# Hard.net
KiCad netlist of a schematic drawn in Altium Designer
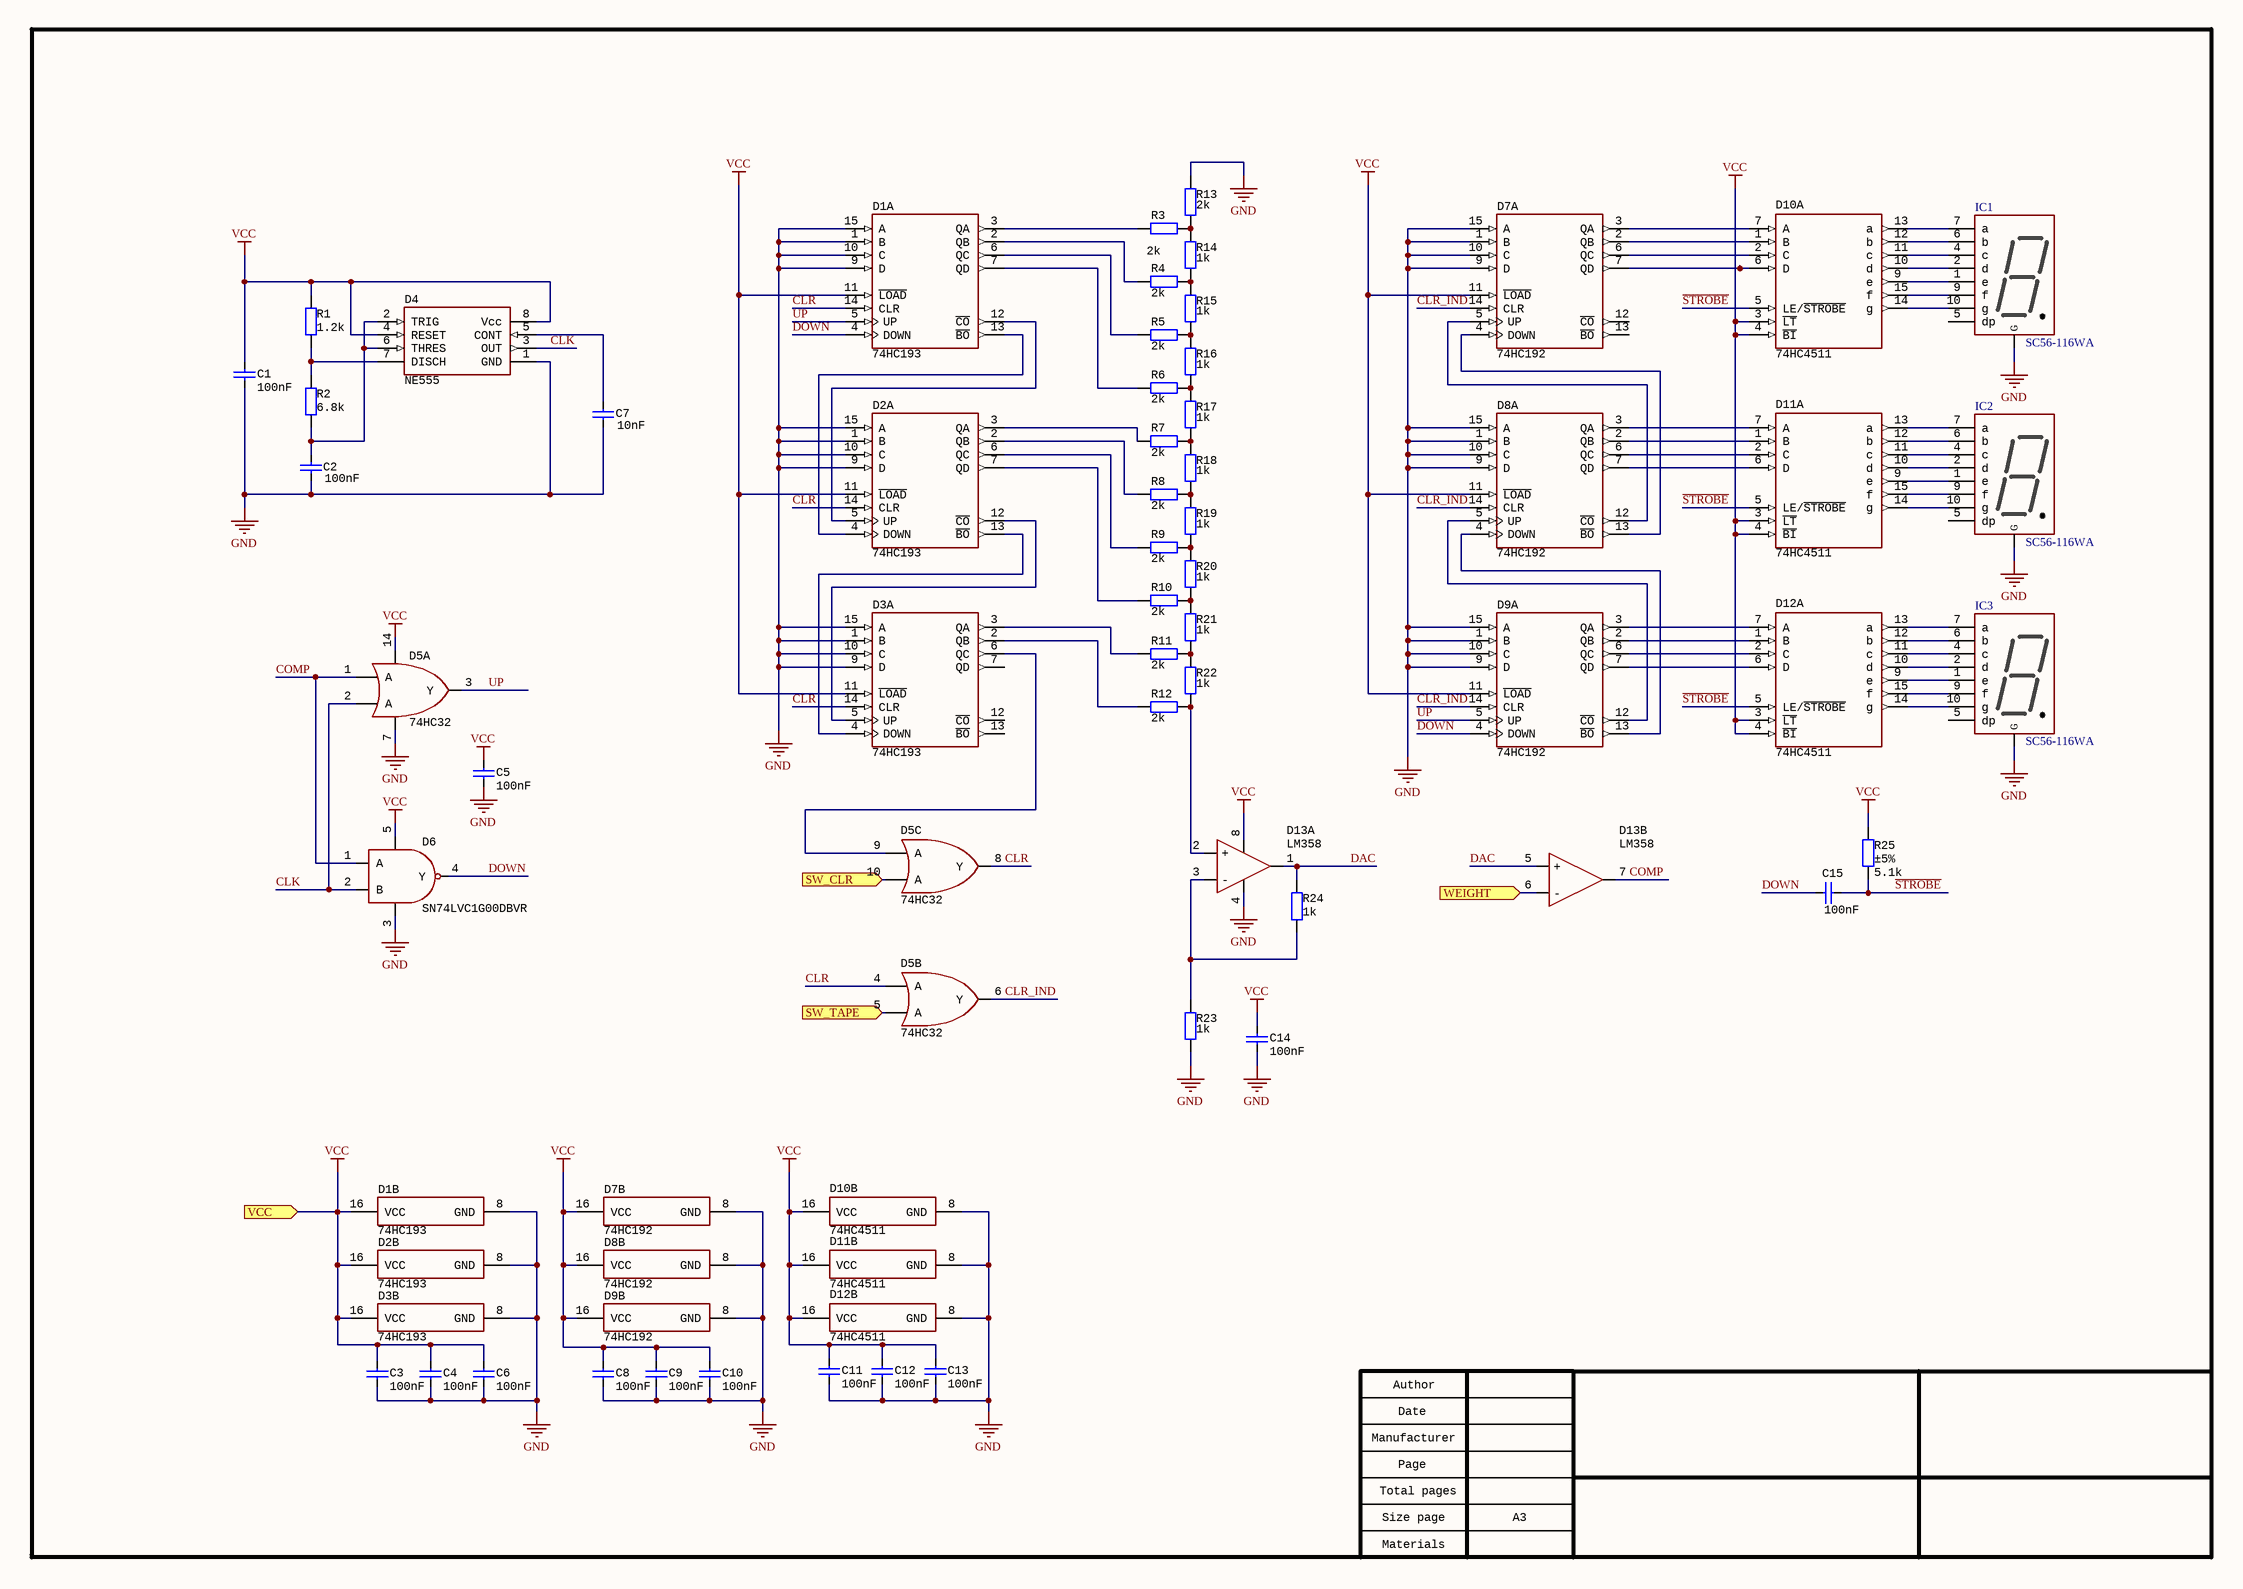
[diagram p0: Hard.SchDoc]

(export (version "E")
  (design (tool "Eeschema 10.0.6"))
  (components
    (comp (ref "C1")
      (value "100nF")
      (footprint "CAP: ECHU(X) K (0603)")
      (fields
        (field (name "MANUFACTURER") "Epcos")
        (field (name "PARTNUMBER") "B32774D4106K000")
        (field (name "VALUEMANUFACTURERPARTNUMBER") "Film capacitor, 100nF, 15VDC, ±10%, 10.9mOhm, 31.5x15 mm, -40...+105°C")
      )
      (libsource (lib "capacitor") (part "Film"))
    )
    (comp (ref "C2")
      (value "100nF")
      (footprint "CAP: ECHU(X) K (0603)")
      (fields
        (field (name "MANUFACTURER") "Epcos")
        (field (name "PARTNUMBER") "B32774D4106K000")
        (field (name "VALUEMANUFACTURERPARTNUMBER") "Film capacitor, 100nF, 15VDC, ±10%, 10.9mOhm, 31.5x15 mm, -40...+105°C")
      )
      (libsource (lib "capacitor") (part "Film"))
    )
    (comp (ref "C3")
      (value "100nF")
      (footprint "CAP: ECHU(X) K (0603)")
      (fields
        (field (name "MANUFACTURER") "Epcos")
        (field (name "PARTNUMBER") "B32774D4106K000")
        (field (name "VALUEMANUFACTURERPARTNUMBER") "Film capacitor, 100nF, 15VDC, ±10%, 10.9mOhm, 31.5x15 mm, -40...+105°C")
      )
      (libsource (lib "capacitor") (part "Film"))
    )
    (comp (ref "C4")
      (value "100nF")
      (footprint "CAP: ECHU(X) K (0603)")
      (fields
        (field (name "MANUFACTURER") "Epcos")
        (field (name "PARTNUMBER") "B32774D4106K000")
        (field (name "VALUEMANUFACTURERPARTNUMBER") "Film capacitor, 100nF, 15VDC, ±10%, 10.9mOhm, 31.5x15 mm, -40...+105°C")
      )
      (libsource (lib "capacitor") (part "Film"))
    )
    (comp (ref "C5")
      (value "100nF")
      (footprint "CAP: ECHU(X) K (0603)")
      (fields
        (field (name "MANUFACTURER") "Epcos")
        (field (name "PARTNUMBER") "B32774D4106K000")
        (field (name "VALUEMANUFACTURERPARTNUMBER") "Film capacitor, 100nF, 15VDC, ±10%, 10.9mOhm, 31.5x15 mm, -40...+105°C")
      )
      (libsource (lib "capacitor") (part "Film"))
    )
    (comp (ref "C6")
      (value "100nF")
      (footprint "CAP: ECHU(X) K (0603)")
      (fields
        (field (name "MANUFACTURER") "Epcos")
        (field (name "PARTNUMBER") "B32774D4106K000")
        (field (name "VALUEMANUFACTURERPARTNUMBER") "Film capacitor, 100nF, 15VDC, ±10%, 10.9mOhm, 31.5x15 mm, -40...+105°C")
      )
      (libsource (lib "capacitor") (part "Film"))
    )
    (comp (ref "C7")
      (value "10nF")
      (footprint "CAP: ECHU(X) K (0603)")
      (fields
        (field (name "MANUFACTURER") "Epcos")
        (field (name "PARTNUMBER") "B32774D4106K000")
        (field (name "VALUEMANUFACTURERPARTNUMBER") "Film capacitor, 10nF, 15VDC, ±10%, 10.9mOhm, 31.5x15 mm, -40...+105°C")
      )
      (libsource (lib "capacitor") (part "Film"))
    )
    (comp (ref "C8")
      (value "100nF")
      (footprint "CAP: ECHU(X) K (0603)")
      (fields
        (field (name "MANUFACTURER") "Epcos")
        (field (name "PARTNUMBER") "B32774D4106K000")
        (field (name "VALUEMANUFACTURERPARTNUMBER") "Film capacitor, 100nF, 15VDC, ±10%, 10.9mOhm, 31.5x15 mm, -40...+105°C")
      )
      (libsource (lib "capacitor") (part "Film"))
    )
    (comp (ref "C9")
      (value "100nF")
      (footprint "CAP: ECHU(X) K (0603)")
      (fields
        (field (name "MANUFACTURER") "Epcos")
        (field (name "PARTNUMBER") "B32774D4106K000")
        (field (name "VALUEMANUFACTURERPARTNUMBER") "Film capacitor, 100nF, 15VDC, ±10%, 10.9mOhm, 31.5x15 mm, -40...+105°C")
      )
      (libsource (lib "capacitor") (part "Film"))
    )
    (comp (ref "C10")
      (value "100nF")
      (footprint "CAP: ECHU(X) K (0603)")
      (fields
        (field (name "MANUFACTURER") "Epcos")
        (field (name "PARTNUMBER") "B32774D4106K000")
        (field (name "VALUEMANUFACTURERPARTNUMBER") "Film capacitor, 100nF, 15VDC, ±10%, 10.9mOhm, 31.5x15 mm, -40...+105°C")
      )
      (libsource (lib "capacitor") (part "Film"))
    )
    (comp (ref "C11")
      (value "100nF")
      (footprint "CAP: ECHU(X) K (0603)")
      (fields
        (field (name "MANUFACTURER") "Epcos")
        (field (name "PARTNUMBER") "B32774D4106K000")
        (field (name "VALUEMANUFACTURERPARTNUMBER") "Film capacitor, 100nF, 15VDC, ±10%, 10.9mOhm, 31.5x15 mm, -40...+105°C")
      )
      (libsource (lib "capacitor") (part "Film"))
    )
    (comp (ref "C12")
      (value "100nF")
      (footprint "CAP: ECHU(X) K (0603)")
      (fields
        (field (name "MANUFACTURER") "Epcos")
        (field (name "PARTNUMBER") "B32774D4106K000")
        (field (name "VALUEMANUFACTURERPARTNUMBER") "Film capacitor, 100nF, 15VDC, ±10%, 10.9mOhm, 31.5x15 mm, -40...+105°C")
      )
      (libsource (lib "capacitor") (part "Film"))
    )
    (comp (ref "C13")
      (value "100nF")
      (footprint "CAP: ECHU(X) K (0603)")
      (fields
        (field (name "MANUFACTURER") "Epcos")
        (field (name "PARTNUMBER") "B32774D4106K000")
        (field (name "VALUEMANUFACTURERPARTNUMBER") "Film capacitor, 100nF, 15VDC, ±10%, 10.9mOhm, 31.5x15 mm, -40...+105°C")
      )
      (libsource (lib "capacitor") (part "Film"))
    )
    (comp (ref "C14")
      (value "100nF")
      (footprint "CAP: ECHU(X) K (0603)")
      (fields
        (field (name "MANUFACTURER") "Epcos")
        (field (name "PARTNUMBER") "B32774D4106K000")
        (field (name "VALUEMANUFACTURERPARTNUMBER") "Film capacitor, 100nF, 15VDC, ±10%, 10.9mOhm, 31.5x15 mm, -40...+105°C")
      )
      (libsource (lib "capacitor") (part "Film"))
    )
    (comp (ref "C15")
      (value "100nF")
      (footprint "CAP: ECHU(X) K (0603)")
      (fields
        (field (name "MANUFACTURER") "Epcos")
        (field (name "PARTNUMBER") "B32774D4106K000")
        (field (name "VALUEMANUFACTURERPARTNUMBER") "Film capacitor, 100nF, 15VDC, ±10%, 10.9mOhm, 31.5x15 mm, -40...+105°C")
      )
      (libsource (lib "capacitor") (part "Film"))
    )
    (comp (ref "D1")
      (value "74HC193")
      (footprint "16-SO")
      (description "Counter")
      (libsource (lib "ic-logic") (part "74HC193"))
    )
    (comp (ref "D2")
      (value "74HC193")
      (footprint "16-SO")
      (description "Counter")
      (libsource (lib "ic-logic") (part "74HC193"))
    )
    (comp (ref "D3")
      (value "74HC193")
      (footprint "16-SO")
      (description "Counter")
      (libsource (lib "ic-logic") (part "74HC193"))
    )
    (comp (ref "D4")
      (value "NE555")
      (footprint "8-SOIC")
      (description "Counter")
      (libsource (lib "ic-logic") (part "NE555"))
    )
    (comp (ref "D5")
      (value "~")
      (footprint "14-SOIC")
      (description "OR")
      (fields
        (field (name "MANUFACTURER") "Texas Instruments")
        (field (name "VALUEMANUFACTURERPARTNUMBER") "IC logic OR, 1.65...5.5V, -40...+125°C, SOT23-6")
        (field (name "PARTNUMBER") "74HC32")
      )
      (libsource (lib "ic-logic") (part "74HC32"))
    )
    (comp (ref "D6")
      (value "~")
      (footprint "SOT23-5")
      (description "NAND")
      (fields
        (field (name "MANUFACTURER") "Texas Instruments")
        (field (name "VALUEMANUFACTURERPARTNUMBER") "IC logic AND, 1.65...5.5V, -40...+125°C, SC-70-5")
        (field (name "PARTNUMBER") "SN74LVC1G00DBVR")
      )
      (libsource (lib "ic-logic") (part "SN74LVC1G00DBVR"))
    )
    (comp (ref "D7")
      (value "74HC192")
      (footprint "16-SO")
      (description "Counter")
      (libsource (lib "ic-logic") (part "74HC192"))
    )
    (comp (ref "D8")
      (value "74HC192")
      (footprint "16-SO")
      (description "Counter")
      (libsource (lib "ic-logic") (part "74HC192"))
    )
    (comp (ref "D9")
      (value "74HC192")
      (footprint "16-SO")
      (description "Counter")
      (libsource (lib "ic-logic") (part "74HC192"))
    )
    (comp (ref "D10")
      (value "74HC4511")
      (footprint "16-SO")
      (description "7-seg decoder")
      (libsource (lib "ic-logic") (part "74HC4511"))
    )
    (comp (ref "D11")
      (value "74HC4511")
      (footprint "16-SO")
      (description "7-seg decoder")
      (libsource (lib "ic-logic") (part "74HC4511"))
    )
    (comp (ref "D12")
      (value "74HC4511")
      (footprint "16-SO")
      (description "7-seg decoder")
      (libsource (lib "ic-logic") (part "74HC4511"))
    )
    (comp (ref "D13")
      (value "LM358")
      (footprint "8-SOIC")
      (description "Comparator")
      (fields
        (field (name "MANUFACTURER") "Microchip Technology")
        (field (name "VALUEMANUFACTURERPARTNUMBER") "IC comparator, Rail-to-Rail, 1.6...5.5V, -40...+85°C, SOT23-5")
      )
      (libsource (lib "ic-op-comp") (part "LM358"))
    )
    (comp (ref "IC1")
      (value "SC56-116WA")
      (footprint "SC56-116WA")
      (libsource (lib "indicator") (part "SC56-116WA"))
    )
    (comp (ref "IC2")
      (value "SC56-116WA")
      (footprint "SC56-116WA")
      (libsource (lib "indicator") (part "SC56-116WA"))
    )
    (comp (ref "IC3")
      (value "SC56-116WA")
      (footprint "SC56-116WA")
      (libsource (lib "indicator") (part "SC56-116WA"))
    )
    (comp (ref "R1")
      (value "1.2k")
      (footprint "RES: 0402")
      (fields
        (field (name "MANUFACTURER") "Yageo")
        (field (name "PARTNUMBER") "RC0201JR-07100RL")
        (field (name "VALUEMANUFACTURERPARTNUMBER") "Resistor film, 1.2k, ±5%, 0201, 0.05W, -55...+125°C")
      )
      (libsource (lib "resistor") (part "Resistor_2"))
    )
    (comp (ref "R2")
      (value "6.8k")
      (footprint "RES: 0402")
      (fields
        (field (name "MANUFACTURER") "Yageo")
        (field (name "PARTNUMBER") "RC0201JR-07100RL")
        (field (name "VALUEMANUFACTURERPARTNUMBER") "Resistor film, 6.8k, ±5%, 0201, 0.05W, -55...+125°C")
      )
      (libsource (lib "resistor") (part "Resistor_2"))
    )
    (comp (ref "R3")
      (value "2k")
      (footprint "RES: 0402")
      (fields
        (field (name "MANUFACTURER") "Yageo")
        (field (name "PARTNUMBER") "RC0201JR-07100RL")
        (field (name "VALUEMANUFACTURERPARTNUMBER") "Resistor film, 2k, ±5%, 0201, 0.05W, -55...+125°C")
      )
      (libsource (lib "") (part "Resistor_2_1"))
    )
    (comp (ref "R4")
      (value "2k")
      (footprint "RES: 0402")
      (fields
        (field (name "MANUFACTURER") "Yageo")
        (field (name "PARTNUMBER") "RC0201JR-07100RL")
        (field (name "VALUEMANUFACTURERPARTNUMBER") "Resistor film, 2k, ±5%, 0201, 0.05W, -55...+125°C")
      )
      (libsource (lib "") (part "Resistor_2_1"))
    )
    (comp (ref "R5")
      (value "2k")
      (footprint "RES: 0402")
      (fields
        (field (name "MANUFACTURER") "Yageo")
        (field (name "PARTNUMBER") "RC0201JR-07100RL")
        (field (name "VALUEMANUFACTURERPARTNUMBER") "Resistor film, 2k, ±5%, 0201, 0.05W, -55...+125°C")
      )
      (libsource (lib "") (part "Resistor_2_1"))
    )
    (comp (ref "R6")
      (value "2k")
      (footprint "RES: 0402")
      (fields
        (field (name "MANUFACTURER") "Yageo")
        (field (name "PARTNUMBER") "RC0201JR-07100RL")
        (field (name "VALUEMANUFACTURERPARTNUMBER") "Resistor film, 2k, ±5%, 0201, 0.05W, -55...+125°C")
      )
      (libsource (lib "") (part "Resistor_2_1"))
    )
    (comp (ref "R7")
      (value "2k")
      (footprint "RES: 0402")
      (fields
        (field (name "MANUFACTURER") "Yageo")
        (field (name "PARTNUMBER") "RC0201JR-07100RL")
        (field (name "VALUEMANUFACTURERPARTNUMBER") "Resistor film, 2k, ±5%, 0201, 0.05W, -55...+125°C")
      )
      (libsource (lib "") (part "Resistor_2_1"))
    )
    (comp (ref "R8")
      (value "2k")
      (footprint "RES: 0402")
      (fields
        (field (name "MANUFACTURER") "Yageo")
        (field (name "PARTNUMBER") "RC0201JR-07100RL")
        (field (name "VALUEMANUFACTURERPARTNUMBER") "Resistor film, 2k, ±5%, 0201, 0.05W, -55...+125°C")
      )
      (libsource (lib "") (part "Resistor_2_1"))
    )
    (comp (ref "R9")
      (value "2k")
      (footprint "RES: 0402")
      (fields
        (field (name "MANUFACTURER") "Yageo")
        (field (name "PARTNUMBER") "RC0201JR-07100RL")
        (field (name "VALUEMANUFACTURERPARTNUMBER") "Resistor film, 2k, ±5%, 0201, 0.05W, -55...+125°C")
      )
      (libsource (lib "") (part "Resistor_2_1"))
    )
    (comp (ref "R10")
      (value "2k")
      (footprint "RES: 0402")
      (fields
        (field (name "MANUFACTURER") "Yageo")
        (field (name "PARTNUMBER") "RC0201JR-07100RL")
        (field (name "VALUEMANUFACTURERPARTNUMBER") "Resistor film, 2k, ±5%, 0201, 0.05W, -55...+125°C")
      )
      (libsource (lib "") (part "Resistor_2_1"))
    )
    (comp (ref "R11")
      (value "2k")
      (footprint "RES: 0402")
      (fields
        (field (name "MANUFACTURER") "Yageo")
        (field (name "PARTNUMBER") "RC0201JR-07100RL")
        (field (name "VALUEMANUFACTURERPARTNUMBER") "Resistor film, 2k, ±5%, 0201, 0.05W, -55...+125°C")
      )
      (libsource (lib "") (part "Resistor_2_1"))
    )
    (comp (ref "R12")
      (value "2k")
      (footprint "RES: 0402")
      (fields
        (field (name "MANUFACTURER") "Yageo")
        (field (name "PARTNUMBER") "RC0201JR-07100RL")
        (field (name "VALUEMANUFACTURERPARTNUMBER") "Resistor film, 2k, ±5%, 0201, 0.05W, -55...+125°C")
      )
      (libsource (lib "") (part "Resistor_2_1"))
    )
    (comp (ref "R13")
      (value "2k")
      (footprint "RES: 0402")
      (fields
        (field (name "MANUFACTURER") "Yageo")
        (field (name "PARTNUMBER") "RC0201JR-07100RL")
        (field (name "VALUEMANUFACTURERPARTNUMBER") "Resistor film, 2k, ±5%, 0201, 0.05W, -55...+125°C")
      )
      (libsource (lib "") (part "Resistor_2_2"))
    )
    (comp (ref "R14")
      (value "1k")
      (footprint "RES: 0402")
      (fields
        (field (name "MANUFACTURER") "Yageo")
        (field (name "PARTNUMBER") "RC0201JR-07100RL")
        (field (name "VALUEMANUFACTURERPARTNUMBER") "Resistor film, 1k, ±5%, 0201, 0.05W, -55...+125°C")
      )
      (libsource (lib "") (part "Resistor_2_2"))
    )
    (comp (ref "R15")
      (value "1k")
      (footprint "RES: 0402")
      (fields
        (field (name "MANUFACTURER") "Yageo")
        (field (name "PARTNUMBER") "RC0201JR-07100RL")
        (field (name "VALUEMANUFACTURERPARTNUMBER") "Resistor film, 1k, ±5%, 0201, 0.05W, -55...+125°C")
      )
      (libsource (lib "") (part "Resistor_2_2"))
    )
    (comp (ref "R16")
      (value "1k")
      (footprint "RES: 0402")
      (fields
        (field (name "MANUFACTURER") "Yageo")
        (field (name "PARTNUMBER") "RC0201JR-07100RL")
        (field (name "VALUEMANUFACTURERPARTNUMBER") "Resistor film, 1k, ±5%, 0201, 0.05W, -55...+125°C")
      )
      (libsource (lib "") (part "Resistor_2_2"))
    )
    (comp (ref "R17")
      (value "1k")
      (footprint "RES: 0402")
      (fields
        (field (name "MANUFACTURER") "Yageo")
        (field (name "PARTNUMBER") "RC0201JR-07100RL")
        (field (name "VALUEMANUFACTURERPARTNUMBER") "Resistor film, 1k, ±5%, 0201, 0.05W, -55...+125°C")
      )
      (libsource (lib "") (part "Resistor_2_2"))
    )
    (comp (ref "R18")
      (value "1k")
      (footprint "RES: 0402")
      (fields
        (field (name "MANUFACTURER") "Yageo")
        (field (name "PARTNUMBER") "RC0201JR-07100RL")
        (field (name "VALUEMANUFACTURERPARTNUMBER") "Resistor film, 1k, ±5%, 0201, 0.05W, -55...+125°C")
      )
      (libsource (lib "") (part "Resistor_2_2"))
    )
    (comp (ref "R19")
      (value "1k")
      (footprint "RES: 0402")
      (fields
        (field (name "MANUFACTURER") "Yageo")
        (field (name "PARTNUMBER") "RC0201JR-07100RL")
        (field (name "VALUEMANUFACTURERPARTNUMBER") "Resistor film, 1k, ±5%, 0201, 0.05W, -55...+125°C")
      )
      (libsource (lib "") (part "Resistor_2_2"))
    )
    (comp (ref "R20")
      (value "1k")
      (footprint "RES: 0402")
      (fields
        (field (name "MANUFACTURER") "Yageo")
        (field (name "PARTNUMBER") "RC0201JR-07100RL")
        (field (name "VALUEMANUFACTURERPARTNUMBER") "Resistor film, 1k, ±5%, 0201, 0.05W, -55...+125°C")
      )
      (libsource (lib "") (part "Resistor_2_2"))
    )
    (comp (ref "R21")
      (value "1k")
      (footprint "RES: 0402")
      (fields
        (field (name "MANUFACTURER") "Yageo")
        (field (name "PARTNUMBER") "RC0201JR-07100RL")
        (field (name "VALUEMANUFACTURERPARTNUMBER") "Resistor film, 1k, ±5%, 0201, 0.05W, -55...+125°C")
      )
      (libsource (lib "") (part "Resistor_2_2"))
    )
    (comp (ref "R22")
      (value "1k")
      (footprint "RES: 0402")
      (fields
        (field (name "MANUFACTURER") "Yageo")
        (field (name "PARTNUMBER") "RC0201JR-07100RL")
        (field (name "VALUEMANUFACTURERPARTNUMBER") "Resistor film, 1k, ±5%, 0201, 0.05W, -55...+125°C")
      )
      (libsource (lib "") (part "Resistor_2_2"))
    )
    (comp (ref "R23")
      (value "1k")
      (footprint "RES: 0402")
      (fields
        (field (name "MANUFACTURER") "Yageo")
        (field (name "PARTNUMBER") "RC0201JR-07100RL")
        (field (name "VALUEMANUFACTURERPARTNUMBER") "Resistor film, 1k, ±5%, 0201, 0.05W, -55...+125°C")
      )
      (libsource (lib "") (part "Resistor_2_2"))
    )
    (comp (ref "R24")
      (value "1k")
      (footprint "RES: 0402")
      (fields
        (field (name "MANUFACTURER") "Yageo")
        (field (name "PARTNUMBER") "RC0201JR-07100RL")
        (field (name "VALUEMANUFACTURERPARTNUMBER") "Resistor film, 1k, ±5%, 0201, 0.05W, -55...+125°C")
      )
      (libsource (lib "resistor") (part "Resistor_2"))
    )
    (comp (ref "R25")
      (value "5.1k")
      (footprint "RES: 0402")
      (fields
        (field (name "MANUFACTURER") "Yageo")
        (field (name "PARTNUMBER") "RC0201JR-07100RL")
        (field (name "VALUEMANUFACTURERPARTNUMBER") "Resistor film, 5.1k, ±5%, 0201, 0.05W, -55...+125°C")
        (field (name "TOLERANCE") "±5%")
      )
      (libsource (lib "") (part "Resistor_2_2"))
    )
  )
  (nets
    (net (code "1") (name "/CLK") (class "Default")
      (node (ref "D4") (pin "3") (pinfunction "OUT_3") (pintype "output"))
      (node (ref "D5") (pin "2") (pinfunction "A_2") (pintype "passive"))
      (node (ref "D6") (pin "2") (pinfunction "B_2") (pintype "passive"))
    )
    (net (code "2") (name "/CLR") (class "Default")
      (node (ref "D1") (pin "14") (pinfunction "CLR_14") (pintype "input"))
      (node (ref "D2") (pin "14") (pinfunction "CLR_14") (pintype "input"))
      (node (ref "D3") (pin "14") (pinfunction "CLR_14") (pintype "input"))
      (node (ref "D5") (pin "4") (pinfunction "A_4") (pintype "passive"))
      (node (ref "D5") (pin "8") (pinfunction "Y_8") (pintype "passive"))
    )
    (net (code "3") (name "/CLR_IND") (class "Default")
      (node (ref "D5") (pin "6") (pinfunction "Y_6") (pintype "passive"))
      (node (ref "D7") (pin "14") (pinfunction "CLR_14") (pintype "input"))
      (node (ref "D8") (pin "14") (pinfunction "CLR_14") (pintype "input"))
      (node (ref "D9") (pin "14") (pinfunction "CLR_14") (pintype "input"))
    )
    (net (code "4") (name "/COMP") (class "Default")
      (node (ref "D13") (pin "7") (pintype "power_in"))
      (node (ref "D5") (pin "1") (pinfunction "A_1") (pintype "passive"))
      (node (ref "D6") (pin "1") (pinfunction "A_1") (pintype "passive"))
    )
    (net (code "5") (name "/DAC") (class "Default")
      (node (ref "D13") (pin "1") (pintype "power_in"))
      (node (ref "D13") (pin "5") (pinfunction "+_5") (pintype "passive"))
      (node (ref "R24") (pin "1") (pinfunction "1_1") (pintype "passive"))
    )
    (net (code "6") (name "/DOWN") (class "Default")
      (node (ref "C15") (pin "1") (pinfunction "1_1") (pintype "passive"))
      (node (ref "D1") (pin "4") (pinfunction "DOWN_4") (pintype "input"))
      (node (ref "D6") (pin "4") (pinfunction "Y_4") (pintype "passive"))
      (node (ref "D9") (pin "4") (pinfunction "DOWN_4") (pintype "input"))
    )
    (net (code "7") (name "/SW_CLR") (class "Default")
      (node (ref "D5") (pin "10") (pinfunction "A_10") (pintype "passive"))
    )
    (net (code "8") (name "/SW_TAPE") (class "Default")
      (node (ref "D5") (pin "5") (pinfunction "A_5") (pintype "passive"))
    )
    (net (code "9") (name "/UP") (class "Default")
      (node (ref "D1") (pin "5") (pinfunction "UP_5") (pintype "input"))
      (node (ref "D5") (pin "3") (pinfunction "Y_3") (pintype "passive"))
      (node (ref "D9") (pin "5") (pinfunction "UP_5") (pintype "input"))
    )
    (net (code "10") (name "/WEIGHT") (class "Default")
      (node (ref "D13") (pin "6") (pinfunction "-_6") (pintype "passive"))
    )
    (net (code "11") (name "/~{STROBE}") (class "Default")
      (node (ref "C15") (pin "2") (pinfunction "2_2") (pintype "passive"))
      (node (ref "D10") (pin "5") (pinfunction "LE/~{STROBE}_5") (pintype "input"))
      (node (ref "D11") (pin "5") (pinfunction "LE/~{STROBE}_5") (pintype "input"))
      (node (ref "D12") (pin "5") (pinfunction "LE/~{STROBE}_5") (pintype "input"))
      (node (ref "R25") (pin "1") (pinfunction "1_1") (pintype "passive"))
    )
    (net (code "12") (name "GND") (class "Default")
      (node (ref "C1") (pin "1") (pinfunction "1_1") (pintype "passive"))
      (node (ref "C10") (pin "1") (pinfunction "1_1") (pintype "passive"))
      (node (ref "C11") (pin "1") (pinfunction "1_1") (pintype "passive"))
      (node (ref "C12") (pin "1") (pinfunction "1_1") (pintype "passive"))
      (node (ref "C13") (pin "1") (pinfunction "1_1") (pintype "passive"))
      (node (ref "C14") (pin "1") (pinfunction "1_1") (pintype "passive"))
      (node (ref "C2") (pin "1") (pinfunction "1_1") (pintype "passive"))
      (node (ref "C3") (pin "1") (pinfunction "1_1") (pintype "passive"))
      (node (ref "C4") (pin "1") (pinfunction "1_1") (pintype "passive"))
      (node (ref "C5") (pin "1") (pinfunction "1_1") (pintype "passive"))
      (node (ref "C6") (pin "1") (pinfunction "1_1") (pintype "passive"))
      (node (ref "C7") (pin "1") (pinfunction "1_1") (pintype "passive"))
      (node (ref "C8") (pin "1") (pinfunction "1_1") (pintype "passive"))
      (node (ref "C9") (pin "1") (pinfunction "1_1") (pintype "passive"))
      (node (ref "D1") (pin "1") (pinfunction "B_1") (pintype "input"))
      (node (ref "D1") (pin "10") (pinfunction "C_10") (pintype "input"))
      (node (ref "D1") (pin "15") (pinfunction "A_15") (pintype "input"))
      (node (ref "D1") (pin "8") (pinfunction "GND_8") (pintype "power_in"))
      (node (ref "D1") (pin "9") (pinfunction "D_9") (pintype "input"))
      (node (ref "D10") (pin "8") (pinfunction "GND_8") (pintype "power_in"))
      (node (ref "D11") (pin "8") (pinfunction "GND_8") (pintype "power_in"))
      (node (ref "D12") (pin "8") (pinfunction "GND_8") (pintype "power_in"))
      (node (ref "D13") (pin "4") (pintype "power_in"))
      (node (ref "D2") (pin "1") (pinfunction "B_1") (pintype "input"))
      (node (ref "D2") (pin "10") (pinfunction "C_10") (pintype "input"))
      (node (ref "D2") (pin "15") (pinfunction "A_15") (pintype "input"))
      (node (ref "D2") (pin "8") (pinfunction "GND_8") (pintype "power_in"))
      (node (ref "D2") (pin "9") (pinfunction "D_9") (pintype "input"))
      (node (ref "D3") (pin "1") (pinfunction "B_1") (pintype "input"))
      (node (ref "D3") (pin "10") (pinfunction "C_10") (pintype "input"))
      (node (ref "D3") (pin "15") (pinfunction "A_15") (pintype "input"))
      (node (ref "D3") (pin "8") (pinfunction "GND_8") (pintype "power_in"))
      (node (ref "D3") (pin "9") (pinfunction "D_9") (pintype "input"))
      (node (ref "D4") (pin "1") (pinfunction "GND_1") (pintype "power_in"))
      (node (ref "D5") (pin "7") (pintype "passive"))
      (node (ref "D6") (pin "3") (pintype "power_in"))
      (node (ref "D7") (pin "1") (pinfunction "B_1") (pintype "input"))
      (node (ref "D7") (pin "10") (pinfunction "C_10") (pintype "input"))
      (node (ref "D7") (pin "15") (pinfunction "A_15") (pintype "input"))
      (node (ref "D7") (pin "8") (pinfunction "GND_8") (pintype "power_in"))
      (node (ref "D7") (pin "9") (pinfunction "D_9") (pintype "input"))
      (node (ref "D8") (pin "1") (pinfunction "B_1") (pintype "input"))
      (node (ref "D8") (pin "10") (pinfunction "C_10") (pintype "input"))
      (node (ref "D8") (pin "15") (pinfunction "A_15") (pintype "input"))
      (node (ref "D8") (pin "8") (pinfunction "GND_8") (pintype "power_in"))
      (node (ref "D8") (pin "9") (pinfunction "D_9") (pintype "input"))
      (node (ref "D9") (pin "1") (pinfunction "B_1") (pintype "input"))
      (node (ref "D9") (pin "10") (pinfunction "C_10") (pintype "input"))
      (node (ref "D9") (pin "15") (pinfunction "A_15") (pintype "input"))
      (node (ref "D9") (pin "8") (pinfunction "GND_8") (pintype "power_in"))
      (node (ref "D9") (pin "9") (pinfunction "D_9") (pintype "input"))
      (node (ref "IC1") (pin "G") (pinfunction "G_G") (pintype "power_in"))
      (node (ref "IC2") (pin "G") (pinfunction "G_G") (pintype "power_in"))
      (node (ref "IC3") (pin "G") (pinfunction "G_G") (pintype "power_in"))
      (node (ref "R13") (pin "2") (pinfunction "2_2") (pintype "passive"))
      (node (ref "R23") (pin "1") (pinfunction "1_1") (pintype "passive"))
    )
    (net (code "13") (name "Net-(D1A-QA)") (class "Default")
      (node (ref "D1") (pin "3") (pinfunction "QA_3") (pintype "output"))
      (node (ref "R3") (pin "2") (pinfunction "2_2") (pintype "passive"))
    )
    (net (code "14") (name "Net-(D1A-QB)") (class "Default")
      (node (ref "D1") (pin "2") (pinfunction "QB_2") (pintype "output"))
      (node (ref "R4") (pin "2") (pinfunction "2_2") (pintype "passive"))
    )
    (net (code "15") (name "Net-(D1A-QC)") (class "Default")
      (node (ref "D1") (pin "6") (pinfunction "QC_6") (pintype "output"))
      (node (ref "R5") (pin "2") (pinfunction "2_2") (pintype "passive"))
    )
    (net (code "16") (name "Net-(D1A-QD)") (class "Default")
      (node (ref "D1") (pin "7") (pinfunction "QD_7") (pintype "output"))
      (node (ref "R6") (pin "2") (pinfunction "2_2") (pintype "passive"))
    )
    (net (code "17") (name "Net-(D1A-~{BO})") (class "Default")
      (node (ref "D1") (pin "13") (pinfunction "~{BO}_13") (pintype "output"))
      (node (ref "D2") (pin "4") (pinfunction "DOWN_4") (pintype "input"))
    )
    (net (code "18") (name "Net-(D1A-~{CO})") (class "Default")
      (node (ref "D1") (pin "12") (pinfunction "~{CO}_12") (pintype "output"))
      (node (ref "D2") (pin "5") (pinfunction "UP_5") (pintype "input"))
    )
    (net (code "19") (name "Net-(D2A-QA)") (class "Default")
      (node (ref "D2") (pin "3") (pinfunction "QA_3") (pintype "output"))
      (node (ref "R7") (pin "2") (pinfunction "2_2") (pintype "passive"))
    )
    (net (code "20") (name "Net-(D2A-QB)") (class "Default")
      (node (ref "D2") (pin "2") (pinfunction "QB_2") (pintype "output"))
      (node (ref "R8") (pin "2") (pinfunction "2_2") (pintype "passive"))
    )
    (net (code "21") (name "Net-(D2A-QC)") (class "Default")
      (node (ref "D2") (pin "6") (pinfunction "QC_6") (pintype "output"))
      (node (ref "R9") (pin "2") (pinfunction "2_2") (pintype "passive"))
    )
    (net (code "22") (name "Net-(D2A-QD)") (class "Default")
      (node (ref "D2") (pin "7") (pinfunction "QD_7") (pintype "output"))
      (node (ref "R10") (pin "2") (pinfunction "2_2") (pintype "passive"))
    )
    (net (code "23") (name "Net-(D2A-~{BO})") (class "Default")
      (node (ref "D2") (pin "13") (pinfunction "~{BO}_13") (pintype "output"))
      (node (ref "D3") (pin "4") (pinfunction "DOWN_4") (pintype "input"))
    )
    (net (code "24") (name "Net-(D2A-~{CO})") (class "Default")
      (node (ref "D2") (pin "12") (pinfunction "~{CO}_12") (pintype "output"))
      (node (ref "D3") (pin "5") (pinfunction "UP_5") (pintype "input"))
    )
    (net (code "25") (name "Net-(D3A-QA)") (class "Default")
      (node (ref "D3") (pin "3") (pinfunction "QA_3") (pintype "output"))
      (node (ref "R11") (pin "2") (pinfunction "2_2") (pintype "passive"))
    )
    (net (code "26") (name "Net-(D3A-QB)") (class "Default")
      (node (ref "D3") (pin "2") (pinfunction "QB_2") (pintype "output"))
      (node (ref "R12") (pin "2") (pinfunction "2_2") (pintype "passive"))
    )
    (net (code "27") (name "Net-(D3A-QC)") (class "Default")
      (node (ref "D3") (pin "6") (pinfunction "QC_6") (pintype "output"))
      (node (ref "D5") (pin "9") (pinfunction "A_9") (pintype "passive"))
    )
    (net (code "28") (name "Net-(D4-CONT)") (class "Default")
      (node (ref "C7") (pin "2") (pinfunction "2_2") (pintype "passive"))
      (node (ref "D4") (pin "5") (pinfunction "CONT_5") (pintype "input"))
    )
    (net (code "29") (name "Net-(D4-DISCH)") (class "Default")
      (node (ref "D4") (pin "7") (pinfunction "DISCH_7") (pintype "passive"))
      (node (ref "R1") (pin "2") (pinfunction "2_2") (pintype "passive"))
      (node (ref "R2") (pin "1") (pinfunction "1_1") (pintype "passive"))
    )
    (net (code "30") (name "Net-(D4-THRES)") (class "Default")
      (node (ref "C2") (pin "2") (pinfunction "2_2") (pintype "passive"))
      (node (ref "D4") (pin "2") (pinfunction "TRIG_2") (pintype "input"))
      (node (ref "D4") (pin "6") (pinfunction "THRES_6") (pintype "input"))
      (node (ref "R2") (pin "2") (pinfunction "2_2") (pintype "passive"))
    )
    (net (code "31") (name "Net-(D7A-DOWN)") (class "Default")
      (node (ref "D7") (pin "4") (pinfunction "DOWN_4") (pintype "input"))
      (node (ref "D8") (pin "13") (pinfunction "~{BO}_13") (pintype "output"))
    )
    (net (code "32") (name "Net-(D7A-UP)") (class "Default")
      (node (ref "D7") (pin "5") (pinfunction "UP_5") (pintype "input"))
      (node (ref "D8") (pin "12") (pinfunction "~{CO}_12") (pintype "output"))
    )
    (net (code "33") (name "Net-(D8A-DOWN)") (class "Default")
      (node (ref "D8") (pin "4") (pinfunction "DOWN_4") (pintype "input"))
      (node (ref "D9") (pin "13") (pinfunction "~{BO}_13") (pintype "output"))
    )
    (net (code "34") (name "Net-(D8A-UP)") (class "Default")
      (node (ref "D8") (pin "5") (pinfunction "UP_5") (pintype "input"))
      (node (ref "D9") (pin "12") (pinfunction "~{CO}_12") (pintype "output"))
    )
    (net (code "35") (name "Net-(D10A-A)") (class "Default")
      (node (ref "D10") (pin "7") (pinfunction "A_7") (pintype "input"))
      (node (ref "D7") (pin "3") (pinfunction "QA_3") (pintype "output"))
    )
    (net (code "36") (name "Net-(D10A-B)") (class "Default")
      (node (ref "D10") (pin "1") (pinfunction "B_1") (pintype "input"))
      (node (ref "D7") (pin "2") (pinfunction "QB_2") (pintype "output"))
    )
    (net (code "37") (name "Net-(D10A-C)") (class "Default")
      (node (ref "D10") (pin "2") (pinfunction "C_2") (pintype "input"))
      (node (ref "D7") (pin "6") (pinfunction "QC_6") (pintype "output"))
    )
    (net (code "38") (name "Net-(D10A-D)") (class "Default")
      (node (ref "D10") (pin "6") (pinfunction "D_6") (pintype "input"))
      (node (ref "D7") (pin "7") (pinfunction "QD_7") (pintype "output"))
    )
    (net (code "39") (name "Net-(D10A-a)") (class "Default")
      (node (ref "D10") (pin "13") (pinfunction "a_13") (pintype "output"))
      (node (ref "IC1") (pin "7") (pinfunction "a_7") (pintype "power_in"))
    )
    (net (code "40") (name "Net-(D10A-b)") (class "Default")
      (node (ref "D10") (pin "12") (pinfunction "b_12") (pintype "output"))
      (node (ref "IC1") (pin "6") (pinfunction "b_6") (pintype "power_in"))
    )
    (net (code "41") (name "Net-(D10A-c)") (class "Default")
      (node (ref "D10") (pin "11") (pinfunction "c_11") (pintype "output"))
      (node (ref "IC1") (pin "4") (pinfunction "c_4") (pintype "power_in"))
    )
    (net (code "42") (name "Net-(D10A-d)") (class "Default")
      (node (ref "D10") (pin "10") (pinfunction "d_10") (pintype "output"))
      (node (ref "IC1") (pin "2") (pinfunction "d_2") (pintype "power_in"))
    )
    (net (code "43") (name "Net-(D10A-e)") (class "Default")
      (node (ref "D10") (pin "9") (pinfunction "e_9") (pintype "output"))
      (node (ref "IC1") (pin "1") (pinfunction "e_1") (pintype "power_in"))
    )
    (net (code "44") (name "Net-(D10A-f)") (class "Default")
      (node (ref "D10") (pin "15") (pinfunction "f_15") (pintype "output"))
      (node (ref "IC1") (pin "9") (pinfunction "f_9") (pintype "power_in"))
    )
    (net (code "45") (name "Net-(D10A-g)") (class "Default")
      (node (ref "D10") (pin "14") (pinfunction "g_14") (pintype "output"))
      (node (ref "IC1") (pin "10") (pinfunction "g_10") (pintype "power_in"))
    )
    (net (code "46") (name "Net-(D11A-A)") (class "Default")
      (node (ref "D11") (pin "7") (pinfunction "A_7") (pintype "input"))
      (node (ref "D8") (pin "3") (pinfunction "QA_3") (pintype "output"))
    )
    (net (code "47") (name "Net-(D11A-B)") (class "Default")
      (node (ref "D11") (pin "1") (pinfunction "B_1") (pintype "input"))
      (node (ref "D8") (pin "2") (pinfunction "QB_2") (pintype "output"))
    )
    (net (code "48") (name "Net-(D11A-C)") (class "Default")
      (node (ref "D11") (pin "2") (pinfunction "C_2") (pintype "input"))
      (node (ref "D8") (pin "6") (pinfunction "QC_6") (pintype "output"))
    )
    (net (code "49") (name "Net-(D11A-D)") (class "Default")
      (node (ref "D11") (pin "6") (pinfunction "D_6") (pintype "input"))
      (node (ref "D8") (pin "7") (pinfunction "QD_7") (pintype "output"))
    )
    (net (code "50") (name "Net-(D11A-a)") (class "Default")
      (node (ref "D11") (pin "13") (pinfunction "a_13") (pintype "output"))
      (node (ref "IC2") (pin "7") (pinfunction "a_7") (pintype "power_in"))
    )
    (net (code "51") (name "Net-(D11A-b)") (class "Default")
      (node (ref "D11") (pin "12") (pinfunction "b_12") (pintype "output"))
      (node (ref "IC2") (pin "6") (pinfunction "b_6") (pintype "power_in"))
    )
    (net (code "52") (name "Net-(D11A-c)") (class "Default")
      (node (ref "D11") (pin "11") (pinfunction "c_11") (pintype "output"))
      (node (ref "IC2") (pin "4") (pinfunction "c_4") (pintype "power_in"))
    )
    (net (code "53") (name "Net-(D11A-d)") (class "Default")
      (node (ref "D11") (pin "10") (pinfunction "d_10") (pintype "output"))
      (node (ref "IC2") (pin "2") (pinfunction "d_2") (pintype "power_in"))
    )
    (net (code "54") (name "Net-(D11A-e)") (class "Default")
      (node (ref "D11") (pin "9") (pinfunction "e_9") (pintype "output"))
      (node (ref "IC2") (pin "1") (pinfunction "e_1") (pintype "power_in"))
    )
    (net (code "55") (name "Net-(D11A-f)") (class "Default")
      (node (ref "D11") (pin "15") (pinfunction "f_15") (pintype "output"))
      (node (ref "IC2") (pin "9") (pinfunction "f_9") (pintype "power_in"))
    )
    (net (code "56") (name "Net-(D11A-g)") (class "Default")
      (node (ref "D11") (pin "14") (pinfunction "g_14") (pintype "output"))
      (node (ref "IC2") (pin "10") (pinfunction "g_10") (pintype "power_in"))
    )
    (net (code "57") (name "Net-(D12A-A)") (class "Default")
      (node (ref "D12") (pin "7") (pinfunction "A_7") (pintype "input"))
      (node (ref "D9") (pin "3") (pinfunction "QA_3") (pintype "output"))
    )
    (net (code "58") (name "Net-(D12A-B)") (class "Default")
      (node (ref "D12") (pin "1") (pinfunction "B_1") (pintype "input"))
      (node (ref "D9") (pin "2") (pinfunction "QB_2") (pintype "output"))
    )
    (net (code "59") (name "Net-(D12A-C)") (class "Default")
      (node (ref "D12") (pin "2") (pinfunction "C_2") (pintype "input"))
      (node (ref "D9") (pin "6") (pinfunction "QC_6") (pintype "output"))
    )
    (net (code "60") (name "Net-(D12A-D)") (class "Default")
      (node (ref "D12") (pin "6") (pinfunction "D_6") (pintype "input"))
      (node (ref "D9") (pin "7") (pinfunction "QD_7") (pintype "output"))
    )
    (net (code "61") (name "Net-(D12A-a)") (class "Default")
      (node (ref "D12") (pin "13") (pinfunction "a_13") (pintype "output"))
      (node (ref "IC3") (pin "7") (pinfunction "a_7") (pintype "power_in"))
    )
    (net (code "62") (name "Net-(D12A-b)") (class "Default")
      (node (ref "D12") (pin "12") (pinfunction "b_12") (pintype "output"))
      (node (ref "IC3") (pin "6") (pinfunction "b_6") (pintype "power_in"))
    )
    (net (code "63") (name "Net-(D12A-c)") (class "Default")
      (node (ref "D12") (pin "11") (pinfunction "c_11") (pintype "output"))
      (node (ref "IC3") (pin "4") (pinfunction "c_4") (pintype "power_in"))
    )
    (net (code "64") (name "Net-(D12A-d)") (class "Default")
      (node (ref "D12") (pin "10") (pinfunction "d_10") (pintype "output"))
      (node (ref "IC3") (pin "2") (pinfunction "d_2") (pintype "power_in"))
    )
    (net (code "65") (name "Net-(D12A-e)") (class "Default")
      (node (ref "D12") (pin "9") (pinfunction "e_9") (pintype "output"))
      (node (ref "IC3") (pin "1") (pinfunction "e_1") (pintype "power_in"))
    )
    (net (code "66") (name "Net-(D12A-f)") (class "Default")
      (node (ref "D12") (pin "15") (pinfunction "f_15") (pintype "output"))
      (node (ref "IC3") (pin "9") (pinfunction "f_9") (pintype "power_in"))
    )
    (net (code "67") (name "Net-(D12A-g)") (class "Default")
      (node (ref "D12") (pin "14") (pinfunction "g_14") (pintype "output"))
      (node (ref "IC3") (pin "10") (pinfunction "g_10") (pintype "power_in"))
    )
    (net (code "68") (name "Net-(D13A-+)") (class "Default")
      (node (ref "D13") (pin "2") (pinfunction "+_2") (pintype "passive"))
      (node (ref "R12") (pin "1") (pinfunction "1_1") (pintype "passive"))
      (node (ref "R22") (pin "1") (pinfunction "1_1") (pintype "passive"))
    )
    (net (code "69") (name "Net-(D13A--)") (class "Default")
      (node (ref "D13") (pin "3") (pinfunction "-_3") (pintype "passive"))
      (node (ref "R23") (pin "2") (pinfunction "2_2") (pintype "passive"))
      (node (ref "R24") (pin "2") (pinfunction "2_2") (pintype "passive"))
    )
    (net (code "70") (name "Net-(R10-Pad1)") (class "Default")
      (node (ref "R10") (pin "1") (pinfunction "1_1") (pintype "passive"))
      (node (ref "R20") (pin "1") (pinfunction "1_1") (pintype "passive"))
      (node (ref "R21") (pin "2") (pinfunction "2_2") (pintype "passive"))
    )
    (net (code "71") (name "Net-(R11-Pad1)") (class "Default")
      (node (ref "R11") (pin "1") (pinfunction "1_1") (pintype "passive"))
      (node (ref "R21") (pin "1") (pinfunction "1_1") (pintype "passive"))
      (node (ref "R22") (pin "2") (pinfunction "2_2") (pintype "passive"))
    )
    (net (code "72") (name "Net-(R13-Pad1)") (class "Default")
      (node (ref "R13") (pin "1") (pinfunction "1_1") (pintype "passive"))
      (node (ref "R14") (pin "2") (pinfunction "2_2") (pintype "passive"))
      (node (ref "R3") (pin "1") (pinfunction "1_1") (pintype "passive"))
    )
    (net (code "73") (name "Net-(R14-Pad1)") (class "Default")
      (node (ref "R14") (pin "1") (pinfunction "1_1") (pintype "passive"))
      (node (ref "R15") (pin "2") (pinfunction "2_2") (pintype "passive"))
      (node (ref "R4") (pin "1") (pinfunction "1_1") (pintype "passive"))
    )
    (net (code "74") (name "Net-(R15-Pad1)") (class "Default")
      (node (ref "R15") (pin "1") (pinfunction "1_1") (pintype "passive"))
      (node (ref "R16") (pin "2") (pinfunction "2_2") (pintype "passive"))
      (node (ref "R5") (pin "1") (pinfunction "1_1") (pintype "passive"))
    )
    (net (code "75") (name "Net-(R16-Pad1)") (class "Default")
      (node (ref "R16") (pin "1") (pinfunction "1_1") (pintype "passive"))
      (node (ref "R17") (pin "2") (pinfunction "2_2") (pintype "passive"))
      (node (ref "R6") (pin "1") (pinfunction "1_1") (pintype "passive"))
    )
    (net (code "76") (name "Net-(R17-Pad1)") (class "Default")
      (node (ref "R17") (pin "1") (pinfunction "1_1") (pintype "passive"))
      (node (ref "R18") (pin "2") (pinfunction "2_2") (pintype "passive"))
      (node (ref "R7") (pin "1") (pinfunction "1_1") (pintype "passive"))
    )
    (net (code "77") (name "Net-(R18-Pad1)") (class "Default")
      (node (ref "R18") (pin "1") (pinfunction "1_1") (pintype "passive"))
      (node (ref "R19") (pin "2") (pinfunction "2_2") (pintype "passive"))
      (node (ref "R8") (pin "1") (pinfunction "1_1") (pintype "passive"))
    )
    (net (code "78") (name "Net-(R19-Pad1)") (class "Default")
      (node (ref "R19") (pin "1") (pinfunction "1_1") (pintype "passive"))
      (node (ref "R20") (pin "2") (pinfunction "2_2") (pintype "passive"))
      (node (ref "R9") (pin "1") (pinfunction "1_1") (pintype "passive"))
    )
    (net (code "79") (name "VCC") (class "Default")
      (node (ref "C1") (pin "2") (pinfunction "2_2") (pintype "passive"))
      (node (ref "C10") (pin "2") (pinfunction "2_2") (pintype "passive"))
      (node (ref "C11") (pin "2") (pinfunction "2_2") (pintype "passive"))
      (node (ref "C12") (pin "2") (pinfunction "2_2") (pintype "passive"))
      (node (ref "C13") (pin "2") (pinfunction "2_2") (pintype "passive"))
      (node (ref "C14") (pin "2") (pinfunction "2_2") (pintype "passive"))
      (node (ref "C3") (pin "2") (pinfunction "2_2") (pintype "passive"))
      (node (ref "C4") (pin "2") (pinfunction "2_2") (pintype "passive"))
      (node (ref "C5") (pin "2") (pinfunction "2_2") (pintype "passive"))
      (node (ref "C6") (pin "2") (pinfunction "2_2") (pintype "passive"))
      (node (ref "C8") (pin "2") (pinfunction "2_2") (pintype "passive"))
      (node (ref "C9") (pin "2") (pinfunction "2_2") (pintype "passive"))
      (node (ref "D1") (pin "11") (pinfunction "~{LOAD}_11") (pintype "input"))
      (node (ref "D1") (pin "16") (pinfunction "VCC_16") (pintype "power_in"))
      (node (ref "D10") (pin "16") (pinfunction "VCC_16") (pintype "power_in"))
      (node (ref "D10") (pin "3") (pinfunction "~{LT}_3") (pintype "input"))
      (node (ref "D10") (pin "4") (pinfunction "~{BI}_4") (pintype "input"))
      (node (ref "D11") (pin "16") (pinfunction "VCC_16") (pintype "power_in"))
      (node (ref "D11") (pin "3") (pinfunction "~{LT}_3") (pintype "input"))
      (node (ref "D11") (pin "4") (pinfunction "~{BI}_4") (pintype "input"))
      (node (ref "D12") (pin "16") (pinfunction "VCC_16") (pintype "power_in"))
      (node (ref "D12") (pin "3") (pinfunction "~{LT}_3") (pintype "input"))
      (node (ref "D12") (pin "4") (pinfunction "~{BI}_4") (pintype "input"))
      (node (ref "D13") (pin "8") (pintype "power_in"))
      (node (ref "D2") (pin "11") (pinfunction "~{LOAD}_11") (pintype "input"))
      (node (ref "D2") (pin "16") (pinfunction "VCC_16") (pintype "power_in"))
      (node (ref "D3") (pin "11") (pinfunction "~{LOAD}_11") (pintype "input"))
      (node (ref "D3") (pin "16") (pinfunction "VCC_16") (pintype "power_in"))
      (node (ref "D4") (pin "4") (pinfunction "RESET_4") (pintype "input"))
      (node (ref "D4") (pin "8") (pinfunction "Vcc_8") (pintype "power_in"))
      (node (ref "D5") (pin "14") (pintype "passive"))
      (node (ref "D6") (pin "5") (pintype "power_in"))
      (node (ref "D7") (pin "11") (pinfunction "~{LOAD}_11") (pintype "input"))
      (node (ref "D7") (pin "16") (pinfunction "VCC_16") (pintype "power_in"))
      (node (ref "D8") (pin "11") (pinfunction "~{LOAD}_11") (pintype "input"))
      (node (ref "D8") (pin "16") (pinfunction "VCC_16") (pintype "power_in"))
      (node (ref "D9") (pin "11") (pinfunction "~{LOAD}_11") (pintype "input"))
      (node (ref "D9") (pin "16") (pinfunction "VCC_16") (pintype "power_in"))
      (node (ref "R1") (pin "1") (pinfunction "1_1") (pintype "passive"))
      (node (ref "R25") (pin "2") (pinfunction "2_2") (pintype "passive"))
    )
    (net (code "80") (name "unconnected-(D3A-QD-Pad7)") (class "Default")
      (node (ref "D3") (pin "7") (pinfunction "QD_7") (pintype "output"))
    )
    (net (code "81") (name "unconnected-(D3A-~{BO}-Pad13)") (class "Default")
      (node (ref "D3") (pin "13") (pinfunction "~{BO}_13") (pintype "output"))
    )
    (net (code "82") (name "unconnected-(D3A-~{CO}-Pad12)") (class "Default")
      (node (ref "D3") (pin "12") (pinfunction "~{CO}_12") (pintype "output"))
    )
    (net (code "83") (name "unconnected-(D7A-~{BO}-Pad13)") (class "Default")
      (node (ref "D7") (pin "13") (pinfunction "~{BO}_13") (pintype "output"))
    )
    (net (code "84") (name "unconnected-(D7A-~{CO}-Pad12)") (class "Default")
      (node (ref "D7") (pin "12") (pinfunction "~{CO}_12") (pintype "output"))
    )
    (net (code "85") (name "unconnected-(IC1-dp-Pad5)") (class "Default")
      (node (ref "IC1") (pin "5") (pinfunction "dp_5") (pintype "power_in"))
    )
    (net (code "86") (name "unconnected-(IC2-dp-Pad5)") (class "Default")
      (node (ref "IC2") (pin "5") (pinfunction "dp_5") (pintype "power_in"))
    )
    (net (code "87") (name "unconnected-(IC3-dp-Pad5)") (class "Default")
      (node (ref "IC3") (pin "5") (pinfunction "dp_5") (pintype "power_in"))
    )
  )
)
